# CW312_ICE40UP_ice40.net
KiCad netlist of a schematic drawn in Altium Designer
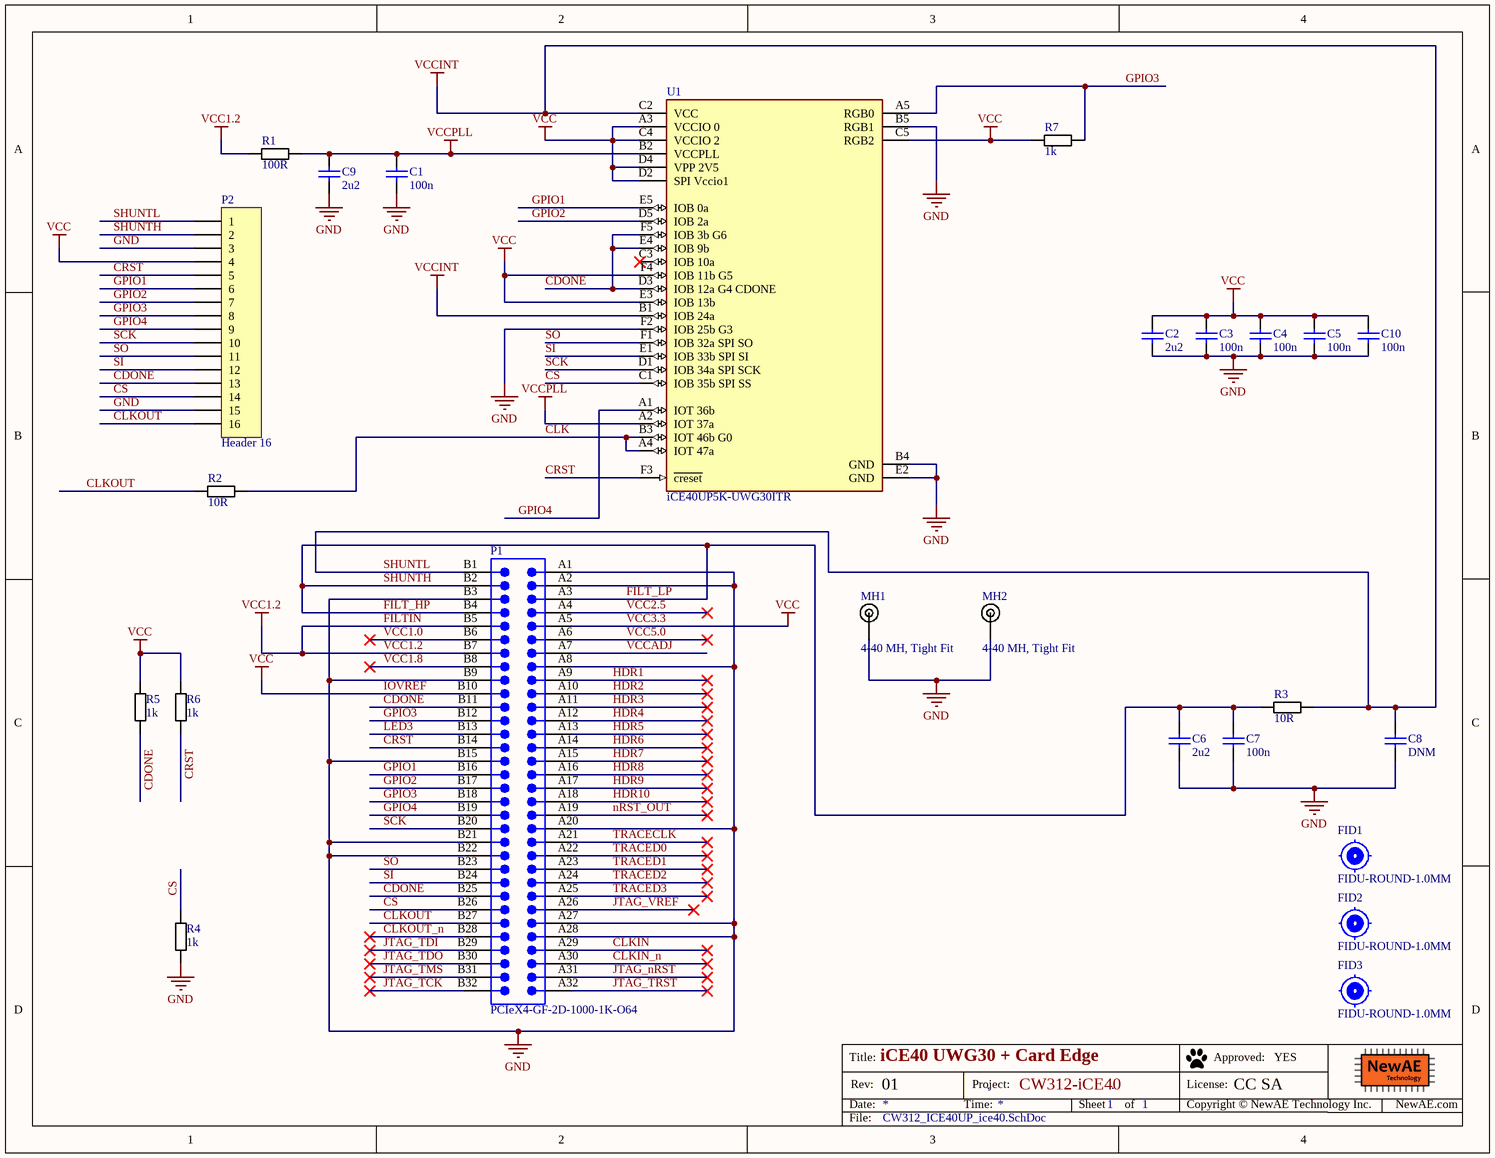
[diagram p0: CW312_ICE40UP_ice40.SchDoc]

(export (version "E")
  (design (tool "Eeschema 10.0.6"))
  (components
    (comp (ref "C1")
      (value "100n")
      (footprint "CAPC0603_M")
      (description "100n, 0603")
      (fields (field (name "PART NUMBER") "CCHIP-100n-0603"))
      (libsource (lib "NewAE_AltiumLib") (part "CAP"))
    )
    (comp (ref "C2")
      (value "2u2")
      (footprint "CAPC0603_M")
      (description "2u2, 0603")
      (fields (field (name "PART NUMBER") "CCHIP-2u2-0603"))
      (libsource (lib "NewAE_AltiumLib") (part "CAP"))
    )
    (comp (ref "C3")
      (value "100n")
      (footprint "CAPC0603_M")
      (description "100n, 0603")
      (fields (field (name "PART NUMBER") "CCHIP-100n-0603"))
      (libsource (lib "NewAE_AltiumLib") (part "CAP"))
    )
    (comp (ref "C4")
      (value "100n")
      (footprint "CAPC0603_M")
      (description "100n, 0603")
      (fields (field (name "PART NUMBER") "CCHIP-100n-0603"))
      (libsource (lib "NewAE_AltiumLib") (part "CAP"))
    )
    (comp (ref "C5")
      (value "100n")
      (footprint "CAPC0603_M")
      (description "100n, 0603")
      (fields (field (name "PART NUMBER") "CCHIP-100n-0603"))
      (libsource (lib "NewAE_AltiumLib") (part "CAP"))
    )
    (comp (ref "C6")
      (value "2u2")
      (footprint "CAPC0603_M")
      (description "2u2, 0603")
      (fields (field (name "PART NUMBER") "CCHIP-2u2-0603"))
      (libsource (lib "NewAE_AltiumLib") (part "CAP"))
    )
    (comp (ref "C7")
      (value "100n")
      (footprint "CAPC0603_M")
      (description "100n, 0603")
      (fields (field (name "PART NUMBER") "CCHIP-100n-0603"))
      (libsource (lib "NewAE_AltiumLib") (part "CAP"))
    )
    (comp (ref "C8")
      (value "DNM")
      (footprint "CAPC0603_M")
      (description "DNM, 0603")
      (fields (field (name "PART NUMBER") "CCHIP-DNM-0603"))
      (libsource (lib "NewAE_AltiumLib") (part "CAP"))
    )
    (comp (ref "C9")
      (value "2u2")
      (footprint "CAPC0603_M")
      (description "2u2, 0603")
      (fields (field (name "PART NUMBER") "CCHIP-2u2-0603"))
      (libsource (lib "NewAE_AltiumLib") (part "CAP"))
    )
    (comp (ref "C10")
      (value "100n")
      (footprint "CAPC0603_M")
      (description "100n, 0603")
      (fields (field (name "PART NUMBER") "CCHIP-100n-0603"))
      (libsource (lib "NewAE_AltiumLib") (part "CAP"))
    )
    (comp (ref "FID1")
      (value "FIDU-ROUND-1.0MM")
      (footprint "FIDU-ROUND-1.0mm")
      (description "ROUND FIDUCIAL")
      (libsource (lib "NewAE_AltiumLib") (part "FIDU-ROUND-1.0MM"))
    )
    (comp (ref "FID2")
      (value "FIDU-ROUND-1.0MM")
      (footprint "FIDU-ROUND-1.0mm")
      (description "ROUND FIDUCIAL")
      (libsource (lib "NewAE_AltiumLib") (part "FIDU-ROUND-1.0MM"))
    )
    (comp (ref "FID3")
      (value "FIDU-ROUND-1.0MM")
      (footprint "FIDU-ROUND-1.0mm")
      (description "ROUND FIDUCIAL")
      (libsource (lib "NewAE_AltiumLib") (part "FIDU-ROUND-1.0MM"))
    )
    (comp (ref "MH1")
      (value "4-40 MH, Tight Fit")
      (footprint "MOUNT_#4_TIGHT")
      (description "Machine screw 4-40 Mounting Hole")
      (fields (field (name "PART NUMBER") "MOUNT_#4_TIGHT"))
      (libsource (lib "NewAE_AltiumLib") (part "Mounting_Hole"))
    )
    (comp (ref "MH2")
      (value "4-40 MH, Tight Fit")
      (footprint "MOUNT_#4_TIGHT")
      (description "Machine screw 4-40 Mounting Hole")
      (fields (field (name "PART NUMBER") "MOUNT_#4_TIGHT"))
      (libsource (lib "NewAE_AltiumLib") (part "Mounting_Hole"))
    )
    (comp (ref "P1")
      (value "PCIeX4-GF-2D-1000-1K-O64")
      (footprint "PCIeX4-GF-2D-1000-1K-O64")
      (description "Golden finger, PCIeX4, Dual, Opposite, Pitch 1mm, 64-Position")
      (fields (field (name "PUBLISHER") "Altium"))
      (libsource (lib "Altium Content Vault") (part "PCIeX4-GF-2D-1000-1K-O64"))
    )
    (comp (ref "P2")
      (value "Header 16")
      (footprint "HDR1X16")
      (description "Header, 16-Pin")
      (fields (field (name "PUBLISHER") "Altium Limited"))
      (libsource (lib "Miscellaneous Connectors") (part "Header 16"))
    )
    (comp (ref "R1")
      (value "100R")
      (footprint "RESC1608X55N")
      (description "100R res, 0603, 1%, 1/10W")
      (fields (field (name "PART NUMBER") "RCHIP-100R-0603") (field (name "TOLERANCE") "1%"))
      (libsource (lib "") (part "RES-EU_2"))
    )
    (comp (ref "R2")
      (value "10R")
      (footprint "RESC1608X55N")
      (description "10R res, 0603, 1%, 1/10W")
      (fields (field (name "PART NUMBER") "RCHIP-10R-0603") (field (name "TOLERANCE") "1%"))
      (libsource (lib "") (part "RES-EU_1"))
    )
    (comp (ref "R3")
      (value "10R")
      (footprint "RESC1608X55N")
      (description "10R res, 0603, 1%, 1/10W")
      (fields (field (name "PART NUMBER") "RCHIP-10R-0603") (field (name "TOLERANCE") "1%"))
      (libsource (lib "") (part "RES-EU_2"))
    )
    (comp (ref "R4")
      (value "1k")
      (footprint "RESC1608X55N")
      (description "1k res, 0603, 1%, 1/10W")
      (fields (field (name "PART NUMBER") "RCHIP-1K-0603") (field (name "TOLERANCE") "1%"))
      (libsource (lib "") (part "RES-EU_3"))
    )
    (comp (ref "R5")
      (value "1k")
      (footprint "RESC1608X55N")
      (description "1k res, 0603, 1%, 1/10W")
      (fields (field (name "PART NUMBER") "RCHIP-1K-0603") (field (name "TOLERANCE") "1%"))
      (libsource (lib "NewAE_AltiumLib") (part "RES-EU"))
    )
    (comp (ref "R6")
      (value "1k")
      (footprint "RESC1608X55N")
      (description "1k res, 0603, 1%, 1/10W")
      (fields (field (name "PART NUMBER") "RCHIP-1K-0603") (field (name "TOLERANCE") "1%"))
      (libsource (lib "NewAE_AltiumLib") (part "RES-EU"))
    )
    (comp (ref "R7")
      (value "1k")
      (footprint "RESC1608X55N")
      (description "1k res, 0603, 1%, 1/10W")
      (fields (field (name "PART NUMBER") "RCHIP-1K-0603") (field (name "TOLERANCE") "1%"))
      (libsource (lib "") (part "RES-EU_1"))
    )
    (comp (ref "U1")
      (value "iCE40UP5K-UWG30ITR")
      (footprint "FP-WLSC-30-MFG")
      (description "CE40-ULTRAPLUS, 5280 LUTS, 1.2V")
      (fields
        (field (name "OCTOPART") "https://octopart.com/ice40up5k-uwg30itr-lattice+semiconductor-75367085")
        (field (name "MANUFACTURER") "Lattice Semiconductor")
      )
      (libsource (lib "Altium Content Vault") (part "3413680a180c2a639ae4d36ae520900"))
    )
  )
  (nets
    (net (code "1") (name "/CDONE") (class "Default")
      (node (ref "P1") (pin "B11") (pinfunction "B11_B11") (pintype "passive"))
      (node (ref "P1") (pin "B25") (pinfunction "B25_B25") (pintype "passive"))
      (node (ref "P2") (pin "13") (pinfunction "13_13") (pintype "passive"))
      (node (ref "R5") (pin "2") (pinfunction "2_2") (pintype "passive"))
      (node (ref "U1") (pin "D3") (pinfunction "IOB_12a_G4_CDONE_D3") (pintype "bidirectional"))
      (node (ref "U1") (pin "E4") (pinfunction "IOB_9b_E4") (pintype "bidirectional"))
      (node (ref "U1") (pin "F5") (pinfunction "IOB_3b_G6_F5") (pintype "bidirectional"))
    )
    (net (code "2") (name "/CLK") (class "Default")
      (node (ref "R2") (pin "1") (pinfunction "1_1") (pintype "passive"))
      (node (ref "U1") (pin "A4") (pinfunction "IOT_47a_A4") (pintype "bidirectional"))
      (node (ref "U1") (pin "B3") (pinfunction "IOT_46b_G0_B3") (pintype "bidirectional"))
    )
    (net (code "3") (name "/CLKIN") (class "Default")
      (node (ref "P1") (pin "A29") (pinfunction "A29_A29") (pintype "passive+no_connect"))
    )
    (net (code "4") (name "/CLKIN_n") (class "Default")
      (node (ref "P1") (pin "A30") (pinfunction "A30_A30") (pintype "passive+no_connect"))
    )
    (net (code "5") (name "/CLKOUT") (class "Default")
      (node (ref "P1") (pin "B27") (pinfunction "B27_B27") (pintype "passive"))
      (node (ref "P2") (pin "16") (pinfunction "16_16") (pintype "passive"))
      (node (ref "R2") (pin "2") (pinfunction "2_2") (pintype "passive"))
    )
    (net (code "6") (name "/CLKOUT_n") (class "Default")
      (node (ref "P1") (pin "B28") (pinfunction "B28_B28") (pintype "passive+no_connect"))
    )
    (net (code "7") (name "/CRST") (class "Default")
      (node (ref "P1") (pin "B14") (pinfunction "B14_B14") (pintype "passive"))
      (node (ref "P2") (pin "5") (pinfunction "5_5") (pintype "passive"))
      (node (ref "R6") (pin "2") (pinfunction "2_2") (pintype "passive"))
      (node (ref "U1") (pin "F3") (pinfunction "~{creset}_F3") (pintype "input"))
    )
    (net (code "8") (name "/CS") (class "Default")
      (node (ref "P1") (pin "B26") (pinfunction "B26_B26") (pintype "passive"))
      (node (ref "P2") (pin "14") (pinfunction "14_14") (pintype "passive"))
      (node (ref "R4") (pin "2") (pinfunction "2_2") (pintype "passive"))
      (node (ref "U1") (pin "C1") (pinfunction "IOB_35b_SPI_SS_C1") (pintype "bidirectional"))
    )
    (net (code "9") (name "/FILT_HP") (class "Default")
      (node (ref "C6") (pin "1") (pinfunction "1_1") (pintype "passive"))
      (node (ref "C7") (pin "1") (pinfunction "1_1") (pintype "passive"))
      (node (ref "P1") (pin "A3") (pinfunction "A3_A3") (pintype "passive"))
      (node (ref "P1") (pin "B2") (pinfunction "B2_B2") (pintype "passive"))
      (node (ref "P1") (pin "B4") (pinfunction "B4_B4") (pintype "passive"))
      (node (ref "P2") (pin "2") (pinfunction "2_2") (pintype "passive"))
      (node (ref "R3") (pin "1") (pinfunction "1_1") (pintype "passive"))
    )
    (net (code "10") (name "/GPIO1") (class "Default")
      (node (ref "P1") (pin "B16") (pinfunction "B16_B16") (pintype "passive"))
      (node (ref "P2") (pin "6") (pinfunction "6_6") (pintype "passive"))
      (node (ref "U1") (pin "E5") (pinfunction "IOB_0a_E5") (pintype "bidirectional"))
    )
    (net (code "11") (name "/GPIO2") (class "Default")
      (node (ref "P1") (pin "B17") (pinfunction "B17_B17") (pintype "passive"))
      (node (ref "P2") (pin "7") (pinfunction "7_7") (pintype "passive"))
      (node (ref "U1") (pin "D5") (pinfunction "IOB_2a_D5") (pintype "bidirectional"))
    )
    (net (code "12") (name "/GPIO3") (class "Default")
      (node (ref "P1") (pin "B12") (pinfunction "B12_B12") (pintype "passive"))
      (node (ref "P1") (pin "B18") (pinfunction "B18_B18") (pintype "passive"))
      (node (ref "P2") (pin "8") (pinfunction "8_8") (pintype "passive"))
      (node (ref "R7") (pin "1") (pinfunction "1_1") (pintype "passive"))
      (node (ref "U1") (pin "A5") (pinfunction "RGB0_A5") (pintype "open_collector"))
    )
    (net (code "13") (name "/GPIO4") (class "Default")
      (node (ref "P1") (pin "B19") (pinfunction "B19_B19") (pintype "passive"))
      (node (ref "P2") (pin "9") (pinfunction "9_9") (pintype "passive"))
      (node (ref "U1") (pin "A1") (pinfunction "IOT_36b_A1") (pintype "bidirectional"))
    )
    (net (code "14") (name "/HDR1") (class "Default")
      (node (ref "P1") (pin "A9") (pinfunction "A9_A9") (pintype "passive+no_connect"))
    )
    (net (code "15") (name "/HDR2") (class "Default")
      (node (ref "P1") (pin "A10") (pinfunction "A10_A10") (pintype "passive+no_connect"))
    )
    (net (code "16") (name "/HDR3") (class "Default")
      (node (ref "P1") (pin "A11") (pinfunction "A11_A11") (pintype "passive+no_connect"))
    )
    (net (code "17") (name "/HDR4") (class "Default")
      (node (ref "P1") (pin "A12") (pinfunction "A12_A12") (pintype "passive+no_connect"))
    )
    (net (code "18") (name "/HDR5") (class "Default")
      (node (ref "P1") (pin "A13") (pinfunction "A13_A13") (pintype "passive+no_connect"))
    )
    (net (code "19") (name "/HDR6") (class "Default")
      (node (ref "P1") (pin "A14") (pinfunction "A14_A14") (pintype "passive+no_connect"))
    )
    (net (code "20") (name "/HDR7") (class "Default")
      (node (ref "P1") (pin "A15") (pinfunction "A15_A15") (pintype "passive+no_connect"))
    )
    (net (code "21") (name "/HDR8") (class "Default")
      (node (ref "P1") (pin "A16") (pinfunction "A16_A16") (pintype "passive+no_connect"))
    )
    (net (code "22") (name "/HDR9") (class "Default")
      (node (ref "P1") (pin "A17") (pinfunction "A17_A17") (pintype "passive+no_connect"))
    )
    (net (code "23") (name "/HDR10") (class "Default")
      (node (ref "P1") (pin "A18") (pinfunction "A18_A18") (pintype "passive+no_connect"))
    )
    (net (code "24") (name "/JTAG_TCK") (class "Default")
      (node (ref "P1") (pin "B32") (pinfunction "B32_B32") (pintype "passive+no_connect"))
    )
    (net (code "25") (name "/JTAG_TDI") (class "Default")
      (node (ref "P1") (pin "B29") (pinfunction "B29_B29") (pintype "passive+no_connect"))
    )
    (net (code "26") (name "/JTAG_TDO") (class "Default")
      (node (ref "P1") (pin "B30") (pinfunction "B30_B30") (pintype "passive+no_connect"))
    )
    (net (code "27") (name "/JTAG_TMS") (class "Default")
      (node (ref "P1") (pin "B31") (pinfunction "B31_B31") (pintype "passive+no_connect"))
    )
    (net (code "28") (name "/JTAG_TRST") (class "Default")
      (node (ref "P1") (pin "A32") (pinfunction "A32_A32") (pintype "passive+no_connect"))
    )
    (net (code "29") (name "/JTAG_VREF") (class "Default")
      (node (ref "P1") (pin "A26") (pinfunction "A26_A26") (pintype "passive+no_connect"))
    )
    (net (code "30") (name "/JTAG_nRST") (class "Default")
      (node (ref "P1") (pin "A31") (pinfunction "A31_A31") (pintype "passive+no_connect"))
    )
    (net (code "31") (name "/LED3") (class "Default")
      (node (ref "P1") (pin "B13") (pinfunction "B13_B13") (pintype "passive"))
    )
    (net (code "32") (name "/SCK") (class "Default")
      (node (ref "P1") (pin "B20") (pinfunction "B20_B20") (pintype "passive"))
      (node (ref "P2") (pin "10") (pinfunction "10_10") (pintype "passive"))
      (node (ref "U1") (pin "D1") (pinfunction "IOB_34a_SPI_SCK_D1") (pintype "bidirectional"))
    )
    (net (code "33") (name "/SI") (class "Default")
      (node (ref "P1") (pin "B24") (pinfunction "B24_B24") (pintype "passive"))
      (node (ref "P2") (pin "12") (pinfunction "12_12") (pintype "passive"))
      (node (ref "U1") (pin "E1") (pinfunction "IOB_33b_SPI_SI_E1") (pintype "bidirectional"))
    )
    (net (code "34") (name "/SO") (class "Default")
      (node (ref "P1") (pin "B23") (pinfunction "B23_B23") (pintype "passive"))
      (node (ref "P2") (pin "11") (pinfunction "11_11") (pintype "passive"))
      (node (ref "U1") (pin "F1") (pinfunction "IOB_32a_SPI_SO_F1") (pintype "bidirectional"))
    )
    (net (code "35") (name "/TRACECLK") (class "Default")
      (node (ref "P1") (pin "A21") (pinfunction "A21_A21") (pintype "passive+no_connect"))
    )
    (net (code "36") (name "/TRACED0") (class "Default")
      (node (ref "P1") (pin "A22") (pinfunction "A22_A22") (pintype "passive+no_connect"))
    )
    (net (code "37") (name "/TRACED1") (class "Default")
      (node (ref "P1") (pin "A23") (pinfunction "A23_A23") (pintype "passive+no_connect"))
    )
    (net (code "38") (name "/TRACED2") (class "Default")
      (node (ref "P1") (pin "A24") (pinfunction "A24_A24") (pintype "passive+no_connect"))
    )
    (net (code "39") (name "/TRACED3") (class "Default")
      (node (ref "P1") (pin "A25") (pinfunction "A25_A25") (pintype "passive+no_connect"))
    )
    (net (code "40") (name "/VCC1.0") (class "Default")
      (node (ref "P1") (pin "B6") (pinfunction "B6_B6") (pintype "passive+no_connect"))
    )
    (net (code "41") (name "/VCC1.8") (class "Default")
      (node (ref "P1") (pin "B8") (pinfunction "B8_B8") (pintype "passive+no_connect"))
    )
    (net (code "42") (name "/VCC2.5") (class "Default")
      (node (ref "P1") (pin "A4") (pinfunction "A4_A4") (pintype "passive+no_connect"))
    )
    (net (code "43") (name "/VCC5.0") (class "Default")
      (node (ref "P1") (pin "A6") (pinfunction "A6_A6") (pintype "passive+no_connect"))
    )
    (net (code "44") (name "/VCCADJ") (class "Default")
      (node (ref "P1") (pin "A7") (pinfunction "A7_A7") (pintype "passive"))
    )
    (net (code "45") (name "/nRST_OUT") (class "Default")
      (node (ref "P1") (pin "A19") (pinfunction "A19_A19") (pintype "passive+no_connect"))
    )
    (net (code "46") (name "GND") (class "Default")
      (node (ref "C1") (pin "2") (pinfunction "2_2") (pintype "passive"))
      (node (ref "C10") (pin "2") (pinfunction "2_2") (pintype "passive"))
      (node (ref "C2") (pin "2") (pinfunction "2_2") (pintype "passive"))
      (node (ref "C3") (pin "2") (pinfunction "2_2") (pintype "passive"))
      (node (ref "C4") (pin "2") (pinfunction "2_2") (pintype "passive"))
      (node (ref "C5") (pin "2") (pinfunction "2_2") (pintype "passive"))
      (node (ref "C6") (pin "2") (pinfunction "2_2") (pintype "passive"))
      (node (ref "C7") (pin "2") (pinfunction "2_2") (pintype "passive"))
      (node (ref "C8") (pin "2") (pinfunction "2_2") (pintype "passive"))
      (node (ref "C9") (pin "2") (pinfunction "2_2") (pintype "passive"))
      (node (ref "MH1") (pin "1") (pinfunction "1_1") (pintype "passive"))
      (node (ref "MH2") (pin "1") (pinfunction "1_1") (pintype "passive"))
      (node (ref "P1") (pin "A1") (pinfunction "A1_A1") (pintype "passive"))
      (node (ref "P1") (pin "A2") (pinfunction "A2_A2") (pintype "passive"))
      (node (ref "P1") (pin "A20") (pinfunction "A20_A20") (pintype "passive"))
      (node (ref "P1") (pin "A27") (pinfunction "A27_A27") (pintype "passive"))
      (node (ref "P1") (pin "A28") (pinfunction "A28_A28") (pintype "passive"))
      (node (ref "P1") (pin "A8") (pinfunction "A8_A8") (pintype "passive"))
      (node (ref "P1") (pin "B15") (pinfunction "B15_B15") (pintype "passive"))
      (node (ref "P1") (pin "B21") (pinfunction "B21_B21") (pintype "passive"))
      (node (ref "P1") (pin "B22") (pinfunction "B22_B22") (pintype "passive"))
      (node (ref "P1") (pin "B3") (pinfunction "B3_B3") (pintype "passive"))
      (node (ref "P1") (pin "B9") (pinfunction "B9_B9") (pintype "passive"))
      (node (ref "P2") (pin "15") (pinfunction "15_15") (pintype "passive"))
      (node (ref "P2") (pin "3") (pinfunction "3_3") (pintype "passive"))
      (node (ref "R4") (pin "1") (pinfunction "1_1") (pintype "passive"))
      (node (ref "U1") (pin "B4") (pinfunction "GND_B4") (pintype "power_in"))
      (node (ref "U1") (pin "B5") (pinfunction "RGB1_B5") (pintype "open_collector"))
      (node (ref "U1") (pin "E2") (pinfunction "GND_E2") (pintype "power_in"))
      (node (ref "U1") (pin "F2") (pinfunction "IOB_25b_G3_F2") (pintype "bidirectional"))
    )
    (net (code "47") (name "VCC") (class "Default")
      (node (ref "C10") (pin "1") (pinfunction "1_1") (pintype "passive"))
      (node (ref "C2") (pin "1") (pinfunction "1_1") (pintype "passive"))
      (node (ref "C3") (pin "1") (pinfunction "1_1") (pintype "passive"))
      (node (ref "C4") (pin "1") (pinfunction "1_1") (pintype "passive"))
      (node (ref "C5") (pin "1") (pinfunction "1_1") (pintype "passive"))
      (node (ref "P1") (pin "A5") (pinfunction "A5_A5") (pintype "passive"))
      (node (ref "P1") (pin "B10") (pinfunction "B10_B10") (pintype "passive"))
      (node (ref "P2") (pin "4") (pinfunction "4_4") (pintype "passive"))
      (node (ref "R5") (pin "1") (pinfunction "1_1") (pintype "passive"))
      (node (ref "R6") (pin "1") (pinfunction "1_1") (pintype "passive"))
      (node (ref "R7") (pin "2") (pinfunction "2_2") (pintype "passive"))
      (node (ref "U1") (pin "A3") (pinfunction "VCCIO_0_A3") (pintype "power_in"))
      (node (ref "U1") (pin "C4") (pinfunction "VCCIO_2_C4") (pintype "power_in"))
      (node (ref "U1") (pin "C5") (pinfunction "RGB2_C5") (pintype "open_collector"))
      (node (ref "U1") (pin "D2") (pinfunction "SPI_Vccio1_D2") (pintype "power_in"))
      (node (ref "U1") (pin "D4") (pinfunction "VPP_2V5_D4") (pintype "power_in"))
      (node (ref "U1") (pin "E3") (pinfunction "IOB_13b_E3") (pintype "bidirectional"))
      (node (ref "U1") (pin "F4") (pinfunction "IOB_11b_G5_F4") (pintype "bidirectional"))
    )
    (net (code "48") (name "VCC1.2") (class "Default")
      (node (ref "P1") (pin "B5") (pinfunction "B5_B5") (pintype "passive"))
      (node (ref "P1") (pin "B7") (pinfunction "B7_B7") (pintype "passive"))
      (node (ref "R1") (pin "1") (pinfunction "1_1") (pintype "passive"))
    )
    (net (code "49") (name "VCCINT") (class "Default")
      (node (ref "C8") (pin "1") (pinfunction "1_1") (pintype "passive"))
      (node (ref "P1") (pin "B1") (pinfunction "B1_B1") (pintype "passive"))
      (node (ref "P2") (pin "1") (pinfunction "1_1") (pintype "passive"))
      (node (ref "R3") (pin "2") (pinfunction "2_2") (pintype "passive"))
      (node (ref "U1") (pin "B1") (pinfunction "IOB_24a_B1") (pintype "bidirectional"))
      (node (ref "U1") (pin "C2") (pinfunction "VCC_C2") (pintype "power_in"))
    )
    (net (code "50") (name "VCCPLL") (class "Default")
      (node (ref "C1") (pin "1") (pinfunction "1_1") (pintype "passive"))
      (node (ref "C9") (pin "1") (pinfunction "1_1") (pintype "passive"))
      (node (ref "R1") (pin "2") (pinfunction "2_2") (pintype "passive"))
      (node (ref "U1") (pin "A2") (pinfunction "IOT_37a_A2") (pintype "bidirectional"))
      (node (ref "U1") (pin "B2") (pinfunction "VCCPLL_B2") (pintype "power_in"))
    )
    (net (code "51") (name "unconnected-(U1-IOB_10a-PadC3)") (class "Default")
      (node (ref "U1") (pin "C3") (pinfunction "IOB_10a_C3") (pintype "bidirectional+no_connect"))
    )
  )
)
